# untitled.net
KiCad netlist of a schematic drawn in EAGLE
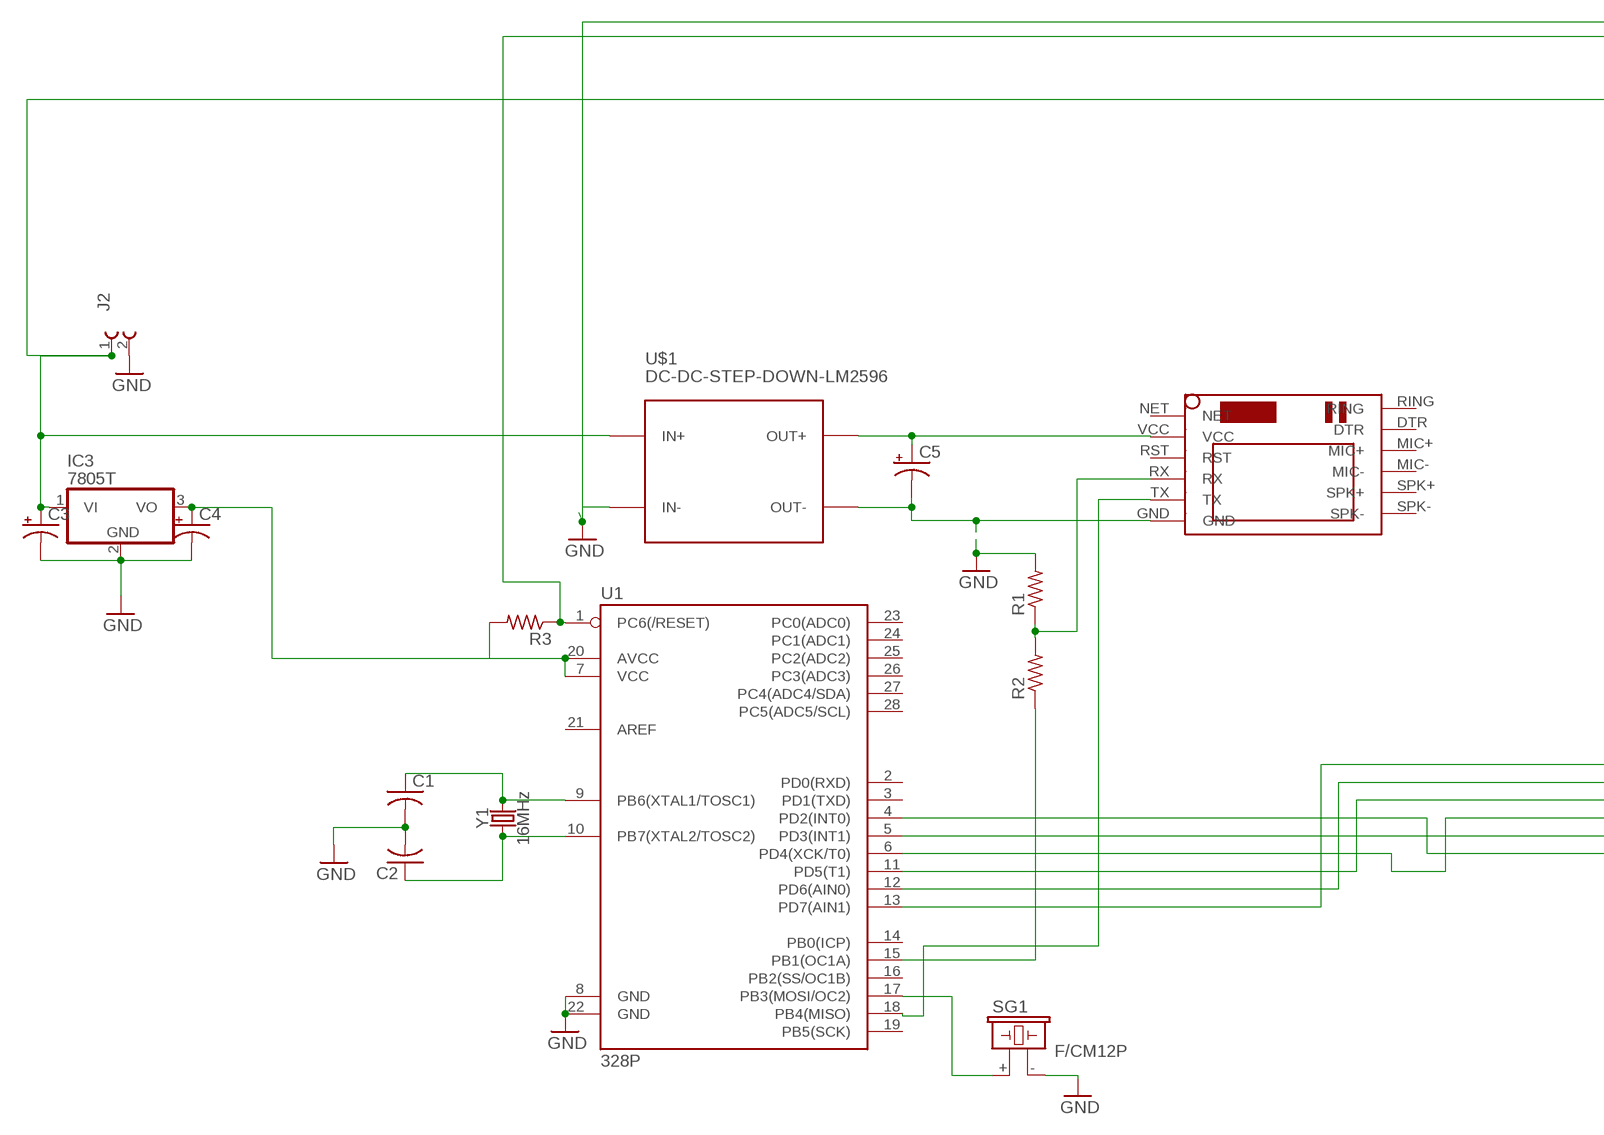
[diagram p0: schematic, sheet 1, part 1 of 2]
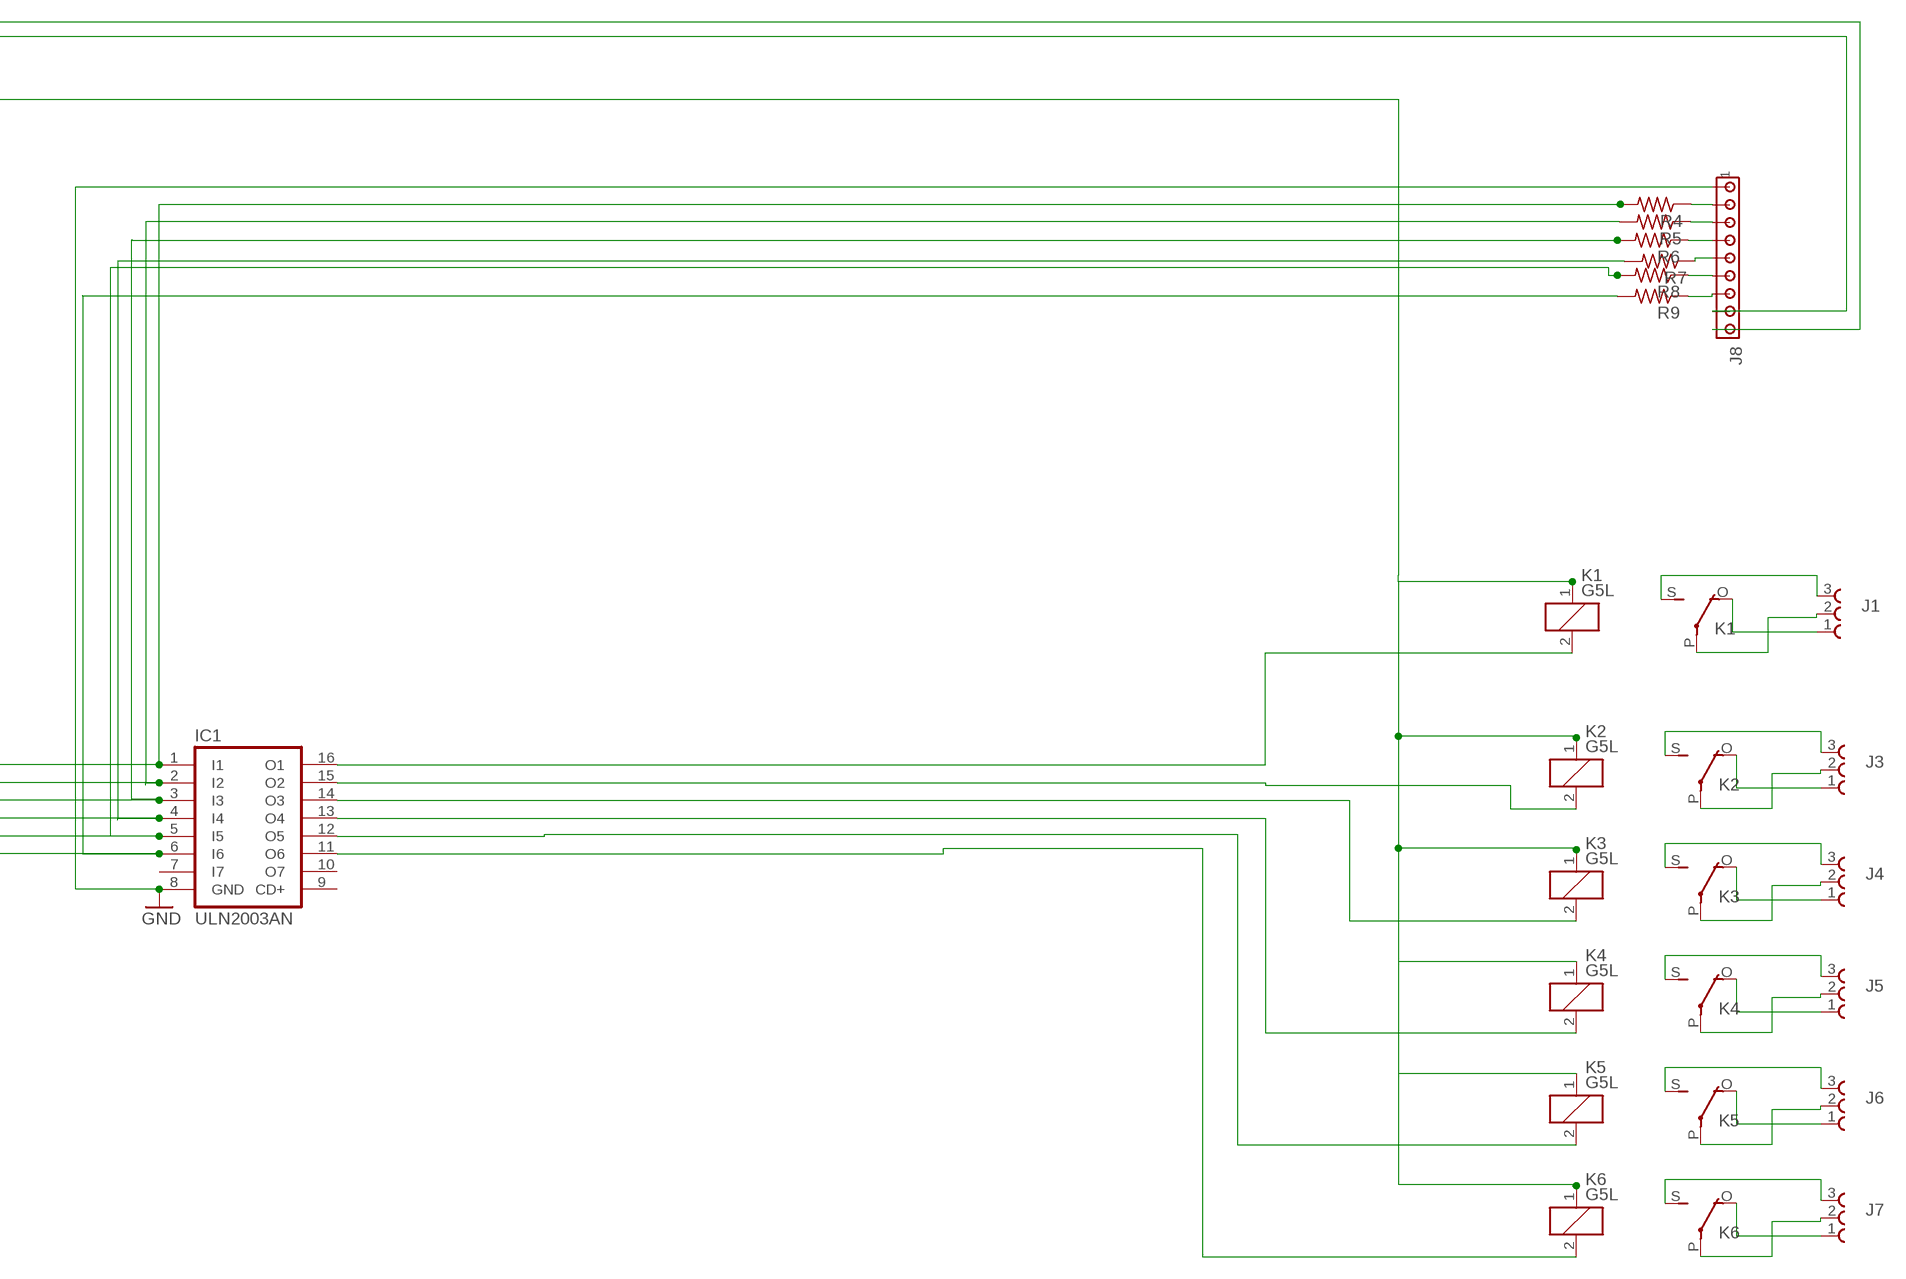
[diagram p1: schematic, sheet 1, part 2 of 2]

(export (version "E")
  (design (tool "Eeschema 10.0.6"))
  (components
    (comp (ref "C1")
      (value "C-US025-024X044")
      (footprint "eagle-import:C025-024X044")
      (libsource (lib "eagle-import") (part "C-US025-024X044"))
    )
    (comp (ref "C2")
      (value "C-US025-024X044")
      (footprint "eagle-import:C025-024X044")
      (libsource (lib "eagle-import") (part "C-US025-024X044"))
    )
    (comp (ref "C3")
      (value "CPOL-USE2.5-5")
      (footprint "eagle-import:E2,5-5")
      (libsource (lib "eagle-import") (part "CPOL-USE2.5-5"))
    )
    (comp (ref "C4")
      (value "CPOL-USE2.5-5")
      (footprint "eagle-import:E2,5-5")
      (libsource (lib "eagle-import") (part "CPOL-USE2.5-5"))
    )
    (comp (ref "C5")
      (value "CAPACITOR-PE5-8.5")
      (footprint "eagle-import:E5-8,5")
      (libsource (lib "eagle-import") (part "CAPACITOR-PE5-8.5"))
    )
    (comp (ref "IC1")
      (value "ULN2003AN")
      (footprint "eagle-import:DIL16")
      (libsource (lib "eagle-import") (part "ULN2003AN"))
    )
    (comp (ref "IC3")
      (value "7805T")
      (footprint "eagle-import:TO220H")
      (libsource (lib "eagle-import") (part "78T05"))
    )
    (comp (ref "J1")
      (value "691216700003")
      (footprint "eagle-import:691216700003")
      (libsource (lib "eagle-import") (part "691216700003"))
    )
    (comp (ref "J2")
      (value "691217910002")
      (footprint "eagle-import:691217910002")
      (libsource (lib "eagle-import") (part "691217910002"))
    )
    (comp (ref "J3")
      (value "691216700003")
      (footprint "eagle-import:691216700003")
      (libsource (lib "eagle-import") (part "691216700003"))
    )
    (comp (ref "J4")
      (value "691216700003")
      (footprint "eagle-import:691216700003")
      (libsource (lib "eagle-import") (part "691216700003"))
    )
    (comp (ref "J5")
      (value "691216700003")
      (footprint "eagle-import:691216700003")
      (libsource (lib "eagle-import") (part "691216700003"))
    )
    (comp (ref "J6")
      (value "691216700003")
      (footprint "eagle-import:691216700003")
      (libsource (lib "eagle-import") (part "691216700003"))
    )
    (comp (ref "J7")
      (value "691216700003")
      (footprint "eagle-import:691216700003")
      (libsource (lib "eagle-import") (part "691216700003"))
    )
    (comp (ref "J8")
      (value "MTA09-100")
      (footprint "eagle-import:10X09MTA")
      (libsource (lib "eagle-import") (part "MTA09-100"))
    )
    (comp (ref "K1")
      (value "G5L")
      (footprint "eagle-import:G5LE")
      (libsource (lib "eagle-import") (part "G5L"))
    )
    (comp (ref "K2")
      (value "G5L")
      (footprint "eagle-import:G5LE")
      (libsource (lib "eagle-import") (part "G5L"))
    )
    (comp (ref "K3")
      (value "G5L")
      (footprint "eagle-import:G5LE")
      (libsource (lib "eagle-import") (part "G5L"))
    )
    (comp (ref "K4")
      (value "G5L")
      (footprint "eagle-import:G5LE")
      (libsource (lib "eagle-import") (part "G5L"))
    )
    (comp (ref "K5")
      (value "G5L")
      (footprint "eagle-import:G5LE")
      (libsource (lib "eagle-import") (part "G5L"))
    )
    (comp (ref "K6")
      (value "G5L")
      (footprint "eagle-import:G5LE")
      (libsource (lib "eagle-import") (part "G5L"))
    )
    (comp (ref "R1")
      (value "R-US_0204/7")
      (footprint "eagle-import:0204_7")
      (libsource (lib "eagle-import") (part "R-US_0204/7"))
    )
    (comp (ref "R2")
      (value "R-US_0204/7")
      (footprint "eagle-import:0204_7")
      (libsource (lib "eagle-import") (part "R-US_0204/7"))
    )
    (comp (ref "R3")
      (value "R-US_0204/7")
      (footprint "eagle-import:0204_7")
      (libsource (lib "eagle-import") (part "R-US_0204/7"))
    )
    (comp (ref "R4")
      (value "R-US_0204/7")
      (footprint "eagle-import:0204_7")
      (libsource (lib "eagle-import") (part "R-US_0204/7"))
    )
    (comp (ref "R5")
      (value "R-US_0204/7")
      (footprint "eagle-import:0204_7")
      (libsource (lib "eagle-import") (part "R-US_0204/7"))
    )
    (comp (ref "R6")
      (value "R-US_0204/7")
      (footprint "eagle-import:0204_7")
      (libsource (lib "eagle-import") (part "R-US_0204/7"))
    )
    (comp (ref "R7")
      (value "R-US_0204/7")
      (footprint "eagle-import:0204_7")
      (libsource (lib "eagle-import") (part "R-US_0204/7"))
    )
    (comp (ref "R8")
      (value "R-US_0204/7")
      (footprint "eagle-import:0204_7")
      (libsource (lib "eagle-import") (part "R-US_0204/7"))
    )
    (comp (ref "R9")
      (value "R-US_0204/7")
      (footprint "eagle-import:0204_7")
      (libsource (lib "eagle-import") (part "R-US_0204/7"))
    )
    (comp (ref "SG1")
      (value "F/CM12P")
      (footprint "eagle-import:F_CM12P")
      (libsource (lib "eagle-import") (part "F/CM12P"))
    )
    (comp (ref "U$1")
      (value "DC-DC-STEP-DOWN-LM2596")
      (footprint "eagle-import:DC-DC-STEP-DOWN-LM2596")
      (libsource (lib "eagle-import") (part "DC-DC-STEP-DOWN-LM2596"))
    )
    (comp (ref "U$2")
      (value "SIM800LMODULE")
      (footprint "eagle-import:SIM800LMODULE")
      (libsource (lib "eagle-import") (part "SIM800LMODULE"))
    )
    (comp (ref "U1")
      (value "328P")
      (footprint "eagle-import:DIP28")
      (libsource (lib "eagle-import") (part "ATMEGA328P_PDIP"))
    )
    (comp (ref "Y1")
      (value "16MHz")
      (footprint "eagle-import:HC49US")
      (libsource (lib "eagle-import") (part "CRYSTAL-16MHZPTH-HC49US"))
    )
  )
  (nets
    (net (code "1") (name "GND") (class "Default")
      (node (ref "C1") (pin "2") (pinfunction "2_2") (pintype "passive"))
      (node (ref "C2") (pin "2") (pinfunction "2_2") (pintype "passive"))
      (node (ref "C3") (pin "-") (pinfunction "-_-") (pintype "passive"))
      (node (ref "C4") (pin "-") (pinfunction "-_-") (pintype "passive"))
      (node (ref "C5") (pin "-") (pinfunction "-_-") (pintype "passive"))
      (node (ref "IC1") (pin "8") (pinfunction "GND_8") (pintype "power_in"))
      (node (ref "IC3") (pin "2") (pinfunction "GND_2") (pintype "passive"))
      (node (ref "J2") (pin "2") (pinfunction "2_2") (pintype "passive"))
      (node (ref "J8") (pin "1") (pinfunction "1_1") (pintype "passive"))
      (node (ref "J8") (pin "9") (pinfunction "9_9") (pintype "passive"))
      (node (ref "R1") (pin "2") (pinfunction "2_2") (pintype "passive"))
      (node (ref "SG1") (pin "-") (pinfunction "2_-") (pintype "passive"))
      (node (ref "U$1") (pin "IN-") (pinfunction "IN-_IN-") (pintype "bidirectional"))
      (node (ref "U$1") (pin "OUT-") (pinfunction "OUT-_OUT-") (pintype "bidirectional"))
      (node (ref "U$2") (pin "GND") (pinfunction "GND_GND") (pintype "bidirectional"))
      (node (ref "U1") (pin "22") (pinfunction "GND_22") (pintype "bidirectional"))
      (node (ref "U1") (pin "8") (pinfunction "GND_8") (pintype "bidirectional"))
    )
    (net (code "2") (name "Net-(C5-Pad+)") (class "Default")
      (node (ref "C5") (pin "+") (pinfunction "+_+") (pintype "passive"))
      (node (ref "U$1") (pin "OUT+") (pinfunction "OUT+_OUT+") (pintype "bidirectional"))
      (node (ref "U$2") (pin "VCC") (pinfunction "VCC_VCC") (pintype "bidirectional"))
    )
    (net (code "3") (name "Net-(IC1-I1)") (class "Default")
      (node (ref "IC1") (pin "1") (pinfunction "I1_1") (pintype "input"))
      (node (ref "R4") (pin "2") (pinfunction "2_2") (pintype "passive"))
      (node (ref "U1") (pin "13") (pinfunction "PD7(AIN1)_13") (pintype "bidirectional"))
    )
    (net (code "4") (name "Net-(IC1-I2)") (class "Default")
      (node (ref "IC1") (pin "2") (pinfunction "I2_2") (pintype "input"))
      (node (ref "R5") (pin "2") (pinfunction "2_2") (pintype "passive"))
      (node (ref "U1") (pin "12") (pinfunction "PD6(AIN0)_12") (pintype "bidirectional"))
    )
    (net (code "5") (name "Net-(IC1-I3)") (class "Default")
      (node (ref "IC1") (pin "3") (pinfunction "I3_3") (pintype "input"))
      (node (ref "R6") (pin "2") (pinfunction "2_2") (pintype "passive"))
      (node (ref "U1") (pin "11") (pinfunction "PD5(T1)_11") (pintype "bidirectional"))
    )
    (net (code "6") (name "Net-(IC1-I4)") (class "Default")
      (node (ref "IC1") (pin "4") (pinfunction "I4_4") (pintype "input"))
      (node (ref "R7") (pin "2") (pinfunction "2_2") (pintype "passive"))
      (node (ref "U1") (pin "6") (pinfunction "PD4(XCK/T0)_6") (pintype "bidirectional"))
    )
    (net (code "7") (name "Net-(IC1-I5)") (class "Default")
      (node (ref "IC1") (pin "5") (pinfunction "I5_5") (pintype "input"))
      (node (ref "R8") (pin "2") (pinfunction "2_2") (pintype "passive"))
      (node (ref "U1") (pin "5") (pinfunction "PD3(INT1)_5") (pintype "bidirectional"))
    )
    (net (code "8") (name "Net-(IC1-I6)") (class "Default")
      (node (ref "IC1") (pin "6") (pinfunction "I6_6") (pintype "input"))
      (node (ref "R9") (pin "2") (pinfunction "2_2") (pintype "passive"))
      (node (ref "U1") (pin "4") (pinfunction "PD2(INT0)_4") (pintype "bidirectional"))
    )
    (net (code "9") (name "Net-(IC1-O1)") (class "Default")
      (node (ref "IC1") (pin "16") (pinfunction "O1_16") (pintype "open_collector"))
      (node (ref "K1") (pin "2") (pinfunction "2_2") (pintype "passive"))
    )
    (net (code "10") (name "Net-(IC1-O2)") (class "Default")
      (node (ref "IC1") (pin "15") (pinfunction "O2_15") (pintype "open_collector"))
      (node (ref "K2") (pin "2") (pinfunction "2_2") (pintype "passive"))
    )
    (net (code "11") (name "Net-(IC1-O3)") (class "Default")
      (node (ref "IC1") (pin "14") (pinfunction "O3_14") (pintype "open_collector"))
      (node (ref "K3") (pin "2") (pinfunction "2_2") (pintype "passive"))
    )
    (net (code "12") (name "Net-(IC1-O4)") (class "Default")
      (node (ref "IC1") (pin "13") (pinfunction "O4_13") (pintype "open_collector"))
      (node (ref "K4") (pin "2") (pinfunction "2_2") (pintype "passive"))
    )
    (net (code "13") (name "Net-(IC1-O5)") (class "Default")
      (node (ref "IC1") (pin "12") (pinfunction "O5_12") (pintype "open_collector"))
      (node (ref "K5") (pin "2") (pinfunction "2_2") (pintype "passive"))
    )
    (net (code "14") (name "Net-(IC1-O6)") (class "Default")
      (node (ref "IC1") (pin "11") (pinfunction "O6_11") (pintype "open_collector"))
      (node (ref "K6") (pin "2") (pinfunction "2_2") (pintype "passive"))
    )
    (net (code "15") (name "Net-(IC3-VI)") (class "Default")
      (node (ref "C3") (pin "+") (pinfunction "+_+") (pintype "passive"))
      (node (ref "IC3") (pin "1") (pinfunction "VI_1") (pintype "input"))
      (node (ref "J2") (pin "1") (pinfunction "1_1") (pintype "passive"))
      (node (ref "K1") (pin "1") (pinfunction "1_1") (pintype "passive"))
      (node (ref "K2") (pin "1") (pinfunction "1_1") (pintype "passive"))
      (node (ref "K3") (pin "1") (pinfunction "1_1") (pintype "passive"))
      (node (ref "K4") (pin "1") (pinfunction "1_1") (pintype "passive"))
      (node (ref "K5") (pin "1") (pinfunction "1_1") (pintype "passive"))
      (node (ref "K6") (pin "1") (pinfunction "1_1") (pintype "passive"))
      (node (ref "U$1") (pin "IN+") (pinfunction "IN+_IN+") (pintype "bidirectional"))
    )
    (net (code "16") (name "Net-(IC3-VO)") (class "Default")
      (node (ref "C4") (pin "+") (pinfunction "+_+") (pintype "passive"))
      (node (ref "IC3") (pin "3") (pinfunction "VO_3") (pintype "passive"))
      (node (ref "R3") (pin "2") (pinfunction "2_2") (pintype "passive"))
      (node (ref "U1") (pin "20") (pinfunction "AVCC_20") (pintype "bidirectional"))
      (node (ref "U1") (pin "7") (pinfunction "VCC_7") (pintype "bidirectional"))
    )
    (net (code "17") (name "Net-(J1-1)") (class "Default")
      (node (ref "J1") (pin "3") (pinfunction "1_3") (pintype "passive"))
      (node (ref "K1") (pin "S") (pinfunction "S_S") (pintype "passive"))
    )
    (net (code "18") (name "Net-(J1-3)") (class "Default")
      (node (ref "J1") (pin "1") (pinfunction "3_1") (pintype "passive"))
      (node (ref "K1") (pin "O") (pinfunction "O_O") (pintype "passive"))
    )
    (net (code "19") (name "Net-(J1-Pad2)") (class "Default")
      (node (ref "J1") (pin "2") (pinfunction "2_2") (pintype "passive"))
      (node (ref "K1") (pin "P") (pinfunction "P_P") (pintype "passive"))
    )
    (net (code "20") (name "Net-(J3-1)") (class "Default")
      (node (ref "J3") (pin "3") (pinfunction "1_3") (pintype "passive"))
      (node (ref "K2") (pin "S") (pinfunction "S_S") (pintype "passive"))
    )
    (net (code "21") (name "Net-(J3-3)") (class "Default")
      (node (ref "J3") (pin "1") (pinfunction "3_1") (pintype "passive"))
      (node (ref "K2") (pin "O") (pinfunction "O_O") (pintype "passive"))
    )
    (net (code "22") (name "Net-(J3-Pad2)") (class "Default")
      (node (ref "J3") (pin "2") (pinfunction "2_2") (pintype "passive"))
      (node (ref "K2") (pin "P") (pinfunction "P_P") (pintype "passive"))
    )
    (net (code "23") (name "Net-(J4-1)") (class "Default")
      (node (ref "J4") (pin "3") (pinfunction "1_3") (pintype "passive"))
      (node (ref "K3") (pin "S") (pinfunction "S_S") (pintype "passive"))
    )
    (net (code "24") (name "Net-(J4-3)") (class "Default")
      (node (ref "J4") (pin "1") (pinfunction "3_1") (pintype "passive"))
      (node (ref "K3") (pin "O") (pinfunction "O_O") (pintype "passive"))
    )
    (net (code "25") (name "Net-(J4-Pad2)") (class "Default")
      (node (ref "J4") (pin "2") (pinfunction "2_2") (pintype "passive"))
      (node (ref "K3") (pin "P") (pinfunction "P_P") (pintype "passive"))
    )
    (net (code "26") (name "Net-(J5-1)") (class "Default")
      (node (ref "J5") (pin "3") (pinfunction "1_3") (pintype "passive"))
      (node (ref "K4") (pin "S") (pinfunction "S_S") (pintype "passive"))
    )
    (net (code "27") (name "Net-(J5-3)") (class "Default")
      (node (ref "J5") (pin "1") (pinfunction "3_1") (pintype "passive"))
      (node (ref "K4") (pin "O") (pinfunction "O_O") (pintype "passive"))
    )
    (net (code "28") (name "Net-(J5-Pad2)") (class "Default")
      (node (ref "J5") (pin "2") (pinfunction "2_2") (pintype "passive"))
      (node (ref "K4") (pin "P") (pinfunction "P_P") (pintype "passive"))
    )
    (net (code "29") (name "Net-(J6-1)") (class "Default")
      (node (ref "J6") (pin "3") (pinfunction "1_3") (pintype "passive"))
      (node (ref "K5") (pin "S") (pinfunction "S_S") (pintype "passive"))
    )
    (net (code "30") (name "Net-(J6-3)") (class "Default")
      (node (ref "J6") (pin "1") (pinfunction "3_1") (pintype "passive"))
      (node (ref "K5") (pin "O") (pinfunction "O_O") (pintype "passive"))
    )
    (net (code "31") (name "Net-(J6-Pad2)") (class "Default")
      (node (ref "J6") (pin "2") (pinfunction "2_2") (pintype "passive"))
      (node (ref "K5") (pin "P") (pinfunction "P_P") (pintype "passive"))
    )
    (net (code "32") (name "Net-(J7-1)") (class "Default")
      (node (ref "J7") (pin "3") (pinfunction "1_3") (pintype "passive"))
      (node (ref "K6") (pin "S") (pinfunction "S_S") (pintype "passive"))
    )
    (net (code "33") (name "Net-(J7-3)") (class "Default")
      (node (ref "J7") (pin "1") (pinfunction "3_1") (pintype "passive"))
      (node (ref "K6") (pin "O") (pinfunction "O_O") (pintype "passive"))
    )
    (net (code "34") (name "Net-(J7-Pad2)") (class "Default")
      (node (ref "J7") (pin "2") (pinfunction "2_2") (pintype "passive"))
      (node (ref "K6") (pin "P") (pinfunction "P_P") (pintype "passive"))
    )
    (net (code "35") (name "Net-(J8-Pad2)") (class "Default")
      (node (ref "J8") (pin "2") (pinfunction "2_2") (pintype "passive"))
      (node (ref "R4") (pin "1") (pinfunction "1_1") (pintype "passive"))
    )
    (net (code "36") (name "Net-(J8-Pad3)") (class "Default")
      (node (ref "J8") (pin "3") (pinfunction "3_3") (pintype "passive"))
      (node (ref "R5") (pin "1") (pinfunction "1_1") (pintype "passive"))
    )
    (net (code "37") (name "Net-(J8-Pad4)") (class "Default")
      (node (ref "J8") (pin "4") (pinfunction "4_4") (pintype "passive"))
      (node (ref "R6") (pin "1") (pinfunction "1_1") (pintype "passive"))
    )
    (net (code "38") (name "Net-(J8-Pad5)") (class "Default")
      (node (ref "J8") (pin "5") (pinfunction "5_5") (pintype "passive"))
      (node (ref "R7") (pin "1") (pinfunction "1_1") (pintype "passive"))
    )
    (net (code "39") (name "Net-(J8-Pad6)") (class "Default")
      (node (ref "J8") (pin "6") (pinfunction "6_6") (pintype "passive"))
      (node (ref "R8") (pin "1") (pinfunction "1_1") (pintype "passive"))
    )
    (net (code "40") (name "Net-(J8-Pad7)") (class "Default")
      (node (ref "J8") (pin "7") (pinfunction "7_7") (pintype "passive"))
      (node (ref "R9") (pin "1") (pinfunction "1_1") (pintype "passive"))
    )
    (net (code "41") (name "Net-(R1-Pad1)") (class "Default")
      (node (ref "R1") (pin "1") (pinfunction "1_1") (pintype "passive"))
      (node (ref "R2") (pin "2") (pinfunction "2_2") (pintype "passive"))
      (node (ref "U$2") (pin "RX") (pinfunction "RX_RX") (pintype "bidirectional"))
    )
    (net (code "42") (name "Net-(SG1-1)") (class "Default")
      (node (ref "SG1") (pin "+") (pinfunction "1_+") (pintype "passive"))
      (node (ref "U1") (pin "17") (pinfunction "PB3(MOSI/OC2)_17") (pintype "bidirectional"))
    )
    (net (code "43") (name "Net-(U1-PB1(OC1A))") (class "Default")
      (node (ref "R2") (pin "1") (pinfunction "1_1") (pintype "passive"))
      (node (ref "U1") (pin "15") (pinfunction "PB1(OC1A)_15") (pintype "bidirectional"))
    )
    (net (code "44") (name "Net-(U1-PB4(MISO))") (class "Default")
      (node (ref "U$2") (pin "TX") (pinfunction "TX_TX") (pintype "bidirectional"))
      (node (ref "U1") (pin "18") (pinfunction "PB4(MISO)_18") (pintype "bidirectional"))
    )
    (net (code "45") (name "Net-(U1-PB6(XTAL1{slash}TOSC1))") (class "Default")
      (node (ref "C1") (pin "1") (pinfunction "1_1") (pintype "passive"))
      (node (ref "U1") (pin "9") (pinfunction "PB6(XTAL1/TOSC1)_9") (pintype "bidirectional"))
      (node (ref "Y1") (pin "2") (pinfunction "2_2") (pintype "passive"))
    )
    (net (code "46") (name "Net-(U1-PB7(XTAL2{slash}TOSC2))") (class "Default")
      (node (ref "C2") (pin "1") (pinfunction "1_1") (pintype "passive"))
      (node (ref "U1") (pin "10") (pinfunction "PB7(XTAL2/TOSC2)_10") (pintype "bidirectional"))
      (node (ref "Y1") (pin "1") (pinfunction "1_1") (pintype "passive"))
    )
    (net (code "47") (name "Net-(U1-PC6({slash}RESET))") (class "Default")
      (node (ref "J8") (pin "8") (pinfunction "8_8") (pintype "passive"))
      (node (ref "R3") (pin "1") (pinfunction "1_1") (pintype "passive"))
      (node (ref "U1") (pin "1") (pinfunction "PC6(/RESET)_1") (pintype "bidirectional"))
    )
    (net (code "48") (name "unconnected-(IC1-CD+-Pad9)") (class "Default")
      (node (ref "IC1") (pin "9") (pinfunction "CD+_9") (pintype "passive"))
    )
    (net (code "49") (name "unconnected-(IC1-I7-Pad7)") (class "Default")
      (node (ref "IC1") (pin "7") (pinfunction "I7_7") (pintype "input"))
    )
    (net (code "50") (name "unconnected-(IC1-O7-Pad10)") (class "Default")
      (node (ref "IC1") (pin "10") (pinfunction "O7_10") (pintype "open_collector"))
    )
    (net (code "51") (name "unconnected-(U$2-PadDTR)") (class "Default")
      (node (ref "U$2") (pin "DTR") (pinfunction "DTR_DTR") (pintype "bidirectional"))
    )
    (net (code "52") (name "unconnected-(U$2-PadMIC+)") (class "Default")
      (node (ref "U$2") (pin "MIC+") (pinfunction "MIC+_MIC+") (pintype "bidirectional"))
    )
    (net (code "53") (name "unconnected-(U$2-PadMIC-)") (class "Default")
      (node (ref "U$2") (pin "MIC-") (pinfunction "MIC-_MIC-") (pintype "bidirectional"))
    )
    (net (code "54") (name "unconnected-(U$2-PadNET)") (class "Default")
      (node (ref "U$2") (pin "NET") (pinfunction "NET_NET") (pintype "bidirectional"))
    )
    (net (code "55") (name "unconnected-(U$2-PadRING)") (class "Default")
      (node (ref "U$2") (pin "RING") (pinfunction "RING_RING") (pintype "bidirectional"))
    )
    (net (code "56") (name "unconnected-(U$2-PadRST)") (class "Default")
      (node (ref "U$2") (pin "RST") (pinfunction "RST_RST") (pintype "bidirectional"))
    )
    (net (code "57") (name "unconnected-(U$2-PadSPK+)") (class "Default")
      (node (ref "U$2") (pin "SPK+") (pinfunction "SPK+_SPK+") (pintype "bidirectional"))
    )
    (net (code "58") (name "unconnected-(U$2-PadSPK-)") (class "Default")
      (node (ref "U$2") (pin "SPK-") (pinfunction "SPK-_SPK-") (pintype "bidirectional"))
    )
    (net (code "59") (name "unconnected-(U1-AREF-Pad21)") (class "Default")
      (node (ref "U1") (pin "21") (pinfunction "AREF_21") (pintype "bidirectional"))
    )
    (net (code "60") (name "unconnected-(U1-PB0(ICP)-Pad14)") (class "Default")
      (node (ref "U1") (pin "14") (pinfunction "PB0(ICP)_14") (pintype "bidirectional"))
    )
    (net (code "61") (name "unconnected-(U1-PB2(SS{slash}OC1B)-Pad16)") (class "Default")
      (node (ref "U1") (pin "16") (pinfunction "PB2(SS/OC1B)_16") (pintype "bidirectional"))
    )
    (net (code "62") (name "unconnected-(U1-PB5(SCK)-Pad19)") (class "Default")
      (node (ref "U1") (pin "19") (pinfunction "PB5(SCK)_19") (pintype "bidirectional"))
    )
    (net (code "63") (name "unconnected-(U1-PC0(ADC0)-Pad23)") (class "Default")
      (node (ref "U1") (pin "23") (pinfunction "PC0(ADC0)_23") (pintype "bidirectional"))
    )
    (net (code "64") (name "unconnected-(U1-PC1(ADC1)-Pad24)") (class "Default")
      (node (ref "U1") (pin "24") (pinfunction "PC1(ADC1)_24") (pintype "bidirectional"))
    )
    (net (code "65") (name "unconnected-(U1-PC2(ADC2)-Pad25)") (class "Default")
      (node (ref "U1") (pin "25") (pinfunction "PC2(ADC2)_25") (pintype "bidirectional"))
    )
    (net (code "66") (name "unconnected-(U1-PC3(ADC3)-Pad26)") (class "Default")
      (node (ref "U1") (pin "26") (pinfunction "PC3(ADC3)_26") (pintype "bidirectional"))
    )
    (net (code "67") (name "unconnected-(U1-PC4(ADC4{slash}SDA)-Pad27)") (class "Default")
      (node (ref "U1") (pin "27") (pinfunction "PC4(ADC4/SDA)_27") (pintype "bidirectional"))
    )
    (net (code "68") (name "unconnected-(U1-PC5(ADC5{slash}SCL)-Pad28)") (class "Default")
      (node (ref "U1") (pin "28") (pinfunction "PC5(ADC5/SCL)_28") (pintype "bidirectional"))
    )
    (net (code "69") (name "unconnected-(U1-PD0(RXD)-Pad2)") (class "Default")
      (node (ref "U1") (pin "2") (pinfunction "PD0(RXD)_2") (pintype "bidirectional"))
    )
    (net (code "70") (name "unconnected-(U1-PD1(TXD)-Pad3)") (class "Default")
      (node (ref "U1") (pin "3") (pinfunction "PD1(TXD)_3") (pintype "bidirectional"))
    )
  )
)
